# PDM_v1.net
KiCad netlist of a schematic drawn in EAGLE
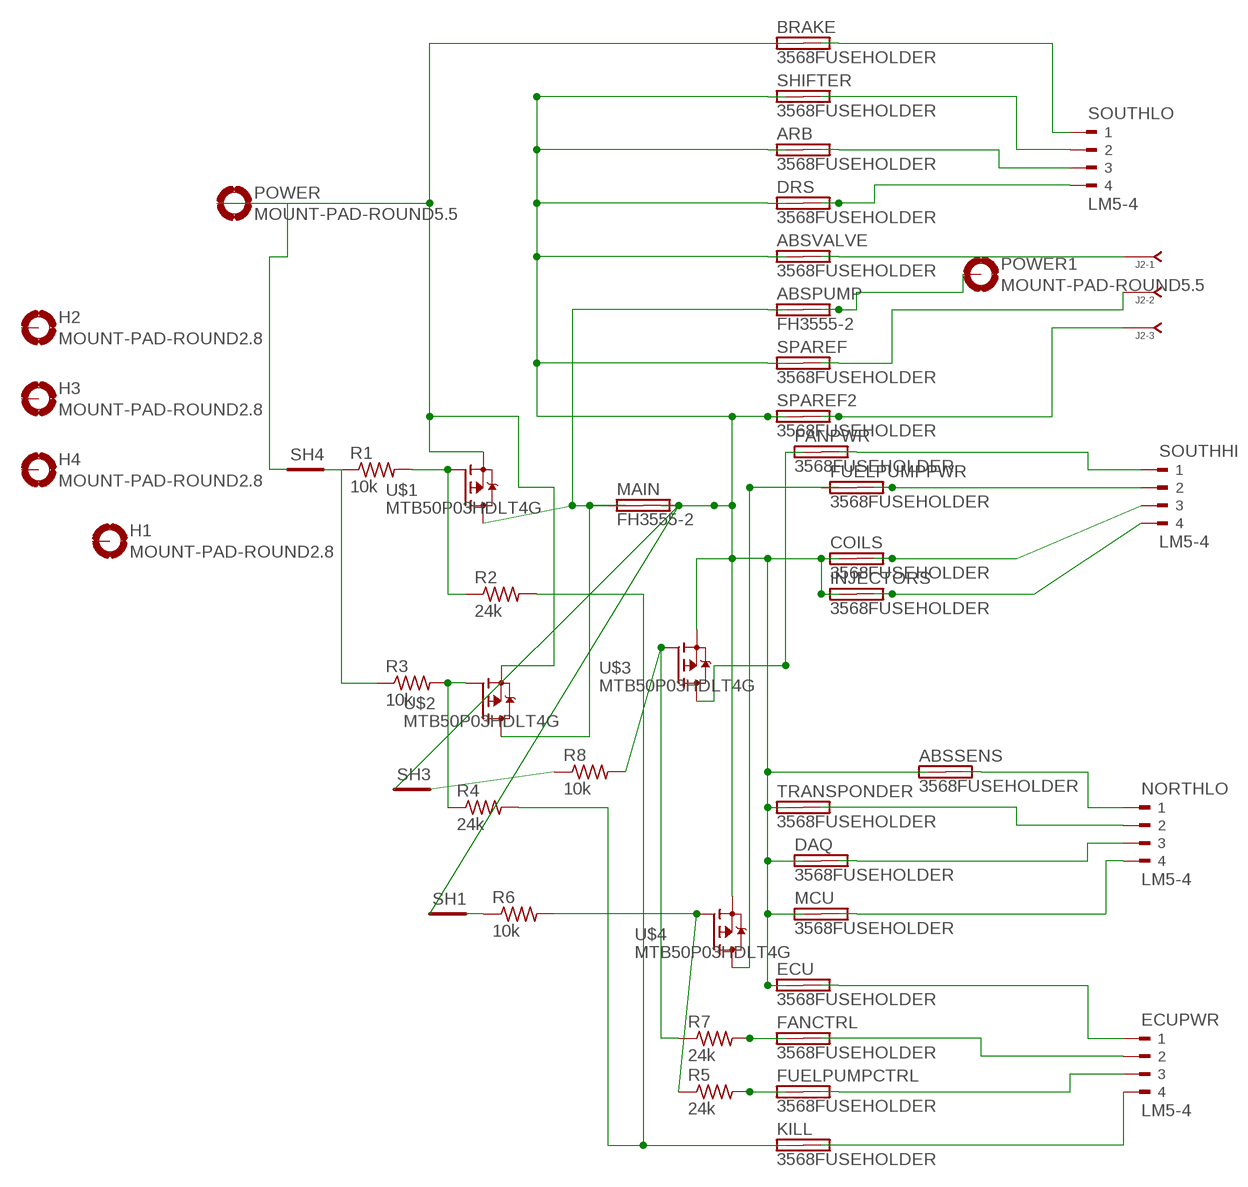
[diagram p0: schematic, sheet 1]

(export (version "E")
  (design (tool "Eeschema 10.0.6"))
  (components
    (comp (ref "ABSPUMP")
      (value "FH3555-2")
      (footprint "eagle-import:3555-2")
      (libsource (lib "eagle-import") (part "FH3555-2"))
    )
    (comp (ref "ABSSENS")
      (value "3568FUSEHOLDER")
      (footprint "eagle-import:3568")
      (libsource (lib "eagle-import") (part "3568FUSEHOLDER"))
    )
    (comp (ref "ABSVALVE")
      (value "3568FUSEHOLDER")
      (footprint "eagle-import:3568")
      (libsource (lib "eagle-import") (part "3568FUSEHOLDER"))
    )
    (comp (ref "ARB")
      (value "3568FUSEHOLDER")
      (footprint "eagle-import:3568")
      (libsource (lib "eagle-import") (part "3568FUSEHOLDER"))
    )
    (comp (ref "BRAKE")
      (value "3568FUSEHOLDER")
      (footprint "eagle-import:3568")
      (libsource (lib "eagle-import") (part "3568FUSEHOLDER"))
    )
    (comp (ref "COILS")
      (value "3568FUSEHOLDER")
      (footprint "eagle-import:3568")
      (libsource (lib "eagle-import") (part "3568FUSEHOLDER"))
    )
    (comp (ref "DAQ")
      (value "3568FUSEHOLDER")
      (footprint "eagle-import:3568")
      (libsource (lib "eagle-import") (part "3568FUSEHOLDER"))
    )
    (comp (ref "DRS")
      (value "3568FUSEHOLDER")
      (footprint "eagle-import:3568")
      (libsource (lib "eagle-import") (part "3568FUSEHOLDER"))
    )
    (comp (ref "ECU")
      (value "3568FUSEHOLDER")
      (footprint "eagle-import:3568")
      (libsource (lib "eagle-import") (part "3568FUSEHOLDER"))
    )
    (comp (ref "ECUPWR")
      (value "LM5-4")
      (footprint "eagle-import:281-1423")
      (libsource (lib "eagle-import") (part "LM5-4"))
    )
    (comp (ref "FANCTRL")
      (value "3568FUSEHOLDER")
      (footprint "eagle-import:3568")
      (libsource (lib "eagle-import") (part "3568FUSEHOLDER"))
    )
    (comp (ref "FANPWR")
      (value "3568FUSEHOLDER")
      (footprint "eagle-import:3568")
      (libsource (lib "eagle-import") (part "3568FUSEHOLDER"))
    )
    (comp (ref "FUELPUMPCTRL")
      (value "3568FUSEHOLDER")
      (footprint "eagle-import:3568")
      (libsource (lib "eagle-import") (part "3568FUSEHOLDER"))
    )
    (comp (ref "FUELPUMPPWR")
      (value "3568FUSEHOLDER")
      (footprint "eagle-import:3568")
      (libsource (lib "eagle-import") (part "3568FUSEHOLDER"))
    )
    (comp (ref "H1")
      (value "MOUNT-PAD-ROUND2.8")
      (footprint "eagle-import:2,8-PAD")
      (libsource (lib "eagle-import") (part "MOUNT-PAD-ROUND2.8"))
    )
    (comp (ref "H2")
      (value "MOUNT-PAD-ROUND2.8")
      (footprint "eagle-import:2,8-PAD")
      (libsource (lib "eagle-import") (part "MOUNT-PAD-ROUND2.8"))
    )
    (comp (ref "H3")
      (value "MOUNT-PAD-ROUND2.8")
      (footprint "eagle-import:2,8-PAD")
      (libsource (lib "eagle-import") (part "MOUNT-PAD-ROUND2.8"))
    )
    (comp (ref "H4")
      (value "MOUNT-PAD-ROUND2.8")
      (footprint "eagle-import:2,8-PAD")
      (libsource (lib "eagle-import") (part "MOUNT-PAD-ROUND2.8"))
    )
    (comp (ref "INJECTORS")
      (value "3568FUSEHOLDER")
      (footprint "eagle-import:3568")
      (libsource (lib "eagle-import") (part "3568FUSEHOLDER"))
    )
    (comp (ref "J2")
      (value "J-04-")
      (footprint "eagle-import:535512-04")
      (libsource (lib "eagle-import") (part "J-04-"))
    )
    (comp (ref "KILL")
      (value "3568FUSEHOLDER")
      (footprint "eagle-import:3568")
      (libsource (lib "eagle-import") (part "3568FUSEHOLDER"))
    )
    (comp (ref "MAIN")
      (value "FH3555-2")
      (footprint "eagle-import:3555-2")
      (libsource (lib "eagle-import") (part "FH3555-2"))
    )
    (comp (ref "MCU")
      (value "3568FUSEHOLDER")
      (footprint "eagle-import:3568")
      (libsource (lib "eagle-import") (part "3568FUSEHOLDER"))
    )
    (comp (ref "NORTHLO")
      (value "LM5-4")
      (footprint "eagle-import:281-1423")
      (libsource (lib "eagle-import") (part "LM5-4"))
    )
    (comp (ref "POWER")
      (value "MOUNT-PAD-ROUND5.5")
      (footprint "eagle-import:5,5-PAD")
      (libsource (lib "eagle-import") (part "MOUNT-PAD-ROUND5.5"))
    )
    (comp (ref "POWER1")
      (value "MOUNT-PAD-ROUND5.5")
      (footprint "eagle-import:5,5-PAD")
      (libsource (lib "eagle-import") (part "MOUNT-PAD-ROUND5.5"))
    )
    (comp (ref "R1")
      (value "10k")
      (footprint "eagle-import:M0805")
      (libsource (lib "eagle-import") (part "R-US_M0805"))
    )
    (comp (ref "R2")
      (value "24k")
      (footprint "eagle-import:M0805")
      (libsource (lib "eagle-import") (part "R-US_M0805"))
    )
    (comp (ref "R3")
      (value "10k")
      (footprint "eagle-import:M0805")
      (libsource (lib "eagle-import") (part "R-US_M0805"))
    )
    (comp (ref "R4")
      (value "24k")
      (footprint "eagle-import:M0805")
      (libsource (lib "eagle-import") (part "R-US_M0805"))
    )
    (comp (ref "R5")
      (value "24k")
      (footprint "eagle-import:M0805")
      (libsource (lib "eagle-import") (part "R-US_M0805"))
    )
    (comp (ref "R6")
      (value "10k")
      (footprint "eagle-import:M0805")
      (libsource (lib "eagle-import") (part "R-US_M0805"))
    )
    (comp (ref "R7")
      (value "24k")
      (footprint "eagle-import:M0805")
      (libsource (lib "eagle-import") (part "R-US_M0805"))
    )
    (comp (ref "R8")
      (value "10k")
      (footprint "eagle-import:M0805")
      (libsource (lib "eagle-import") (part "R-US_M0805"))
    )
    (comp (ref "SH1")
      (value "SHORTA5")
      (footprint "eagle-import:SHORT_ALL-50")
      (libsource (lib "eagle-import") (part "SHORTA5"))
    )
    (comp (ref "SH3")
      (value "SHORTA5")
      (footprint "eagle-import:SHORT_ALL-50")
      (libsource (lib "eagle-import") (part "SHORTA5"))
    )
    (comp (ref "SH4")
      (value "SHORTA5")
      (footprint "eagle-import:SHORT_ALL-50")
      (libsource (lib "eagle-import") (part "SHORTA5"))
    )
    (comp (ref "SHIFTER")
      (value "3568FUSEHOLDER")
      (footprint "eagle-import:3568")
      (libsource (lib "eagle-import") (part "3568FUSEHOLDER"))
    )
    (comp (ref "SOUTHHI")
      (value "LM5-4")
      (footprint "eagle-import:281-1423")
      (libsource (lib "eagle-import") (part "LM5-4"))
    )
    (comp (ref "SOUTHLO")
      (value "LM5-4")
      (footprint "eagle-import:281-1423")
      (libsource (lib "eagle-import") (part "LM5-4"))
    )
    (comp (ref "SPAREF")
      (value "3568FUSEHOLDER")
      (footprint "eagle-import:3568")
      (libsource (lib "eagle-import") (part "3568FUSEHOLDER"))
    )
    (comp (ref "SPAREF2")
      (value "3568FUSEHOLDER")
      (footprint "eagle-import:3568")
      (libsource (lib "eagle-import") (part "3568FUSEHOLDER"))
    )
    (comp (ref "TRANSPONDER")
      (value "3568FUSEHOLDER")
      (footprint "eagle-import:3568")
      (libsource (lib "eagle-import") (part "3568FUSEHOLDER"))
    )
    (comp (ref "U$1")
      (value "MTB50P03HDLT4G")
      (footprint "eagle-import:TO263")
      (libsource (lib "eagle-import") (part "MTB50P03HDLT4G"))
    )
    (comp (ref "U$2")
      (value "MTB50P03HDLT4G")
      (footprint "eagle-import:TO263")
      (libsource (lib "eagle-import") (part "MTB50P03HDLT4G"))
    )
    (comp (ref "U$3")
      (value "MTB50P03HDLT4G")
      (footprint "eagle-import:TO263")
      (libsource (lib "eagle-import") (part "MTB50P03HDLT4G"))
    )
    (comp (ref "U$4")
      (value "MTB50P03HDLT4G")
      (footprint "eagle-import:TO263")
      (libsource (lib "eagle-import") (part "MTB50P03HDLT4G"))
    )
  )
  (nets
    (net (code "1") (name "Net-(ABSPUMP-1A)") (class "Default")
      (node (ref "ABSPUMP") (pin "L1") (pinfunction "1A_L1") (pintype "passive"))
      (node (ref "ABSPUMP") (pin "L2") (pinfunction "1B_L2") (pintype "passive"))
      (node (ref "MAIN") (pin "L1") (pinfunction "1A_L1") (pintype "passive"))
      (node (ref "MAIN") (pin "L2") (pinfunction "1B_L2") (pintype "passive"))
      (node (ref "U$1") (pin "3") (pinfunction "D_3") (pintype "passive"))
      (node (ref "U$2") (pin "3") (pinfunction "D_3") (pintype "passive"))
    )
    (net (code "2") (name "Net-(ABSPUMP-2A)") (class "Default")
      (node (ref "ABSPUMP") (pin "R1") (pinfunction "2A_R1") (pintype "passive"))
      (node (ref "ABSPUMP") (pin "R2") (pinfunction "2B_R2") (pintype "passive"))
      (node (ref "POWER1") (pin "B5,5") (pinfunction "MOUNT_B5,5") (pintype "passive"))
    )
    (net (code "3") (name "Net-(ABSSENS-1A)") (class "Default")
      (node (ref "ABSSENS") (pin "L1") (pinfunction "1A_L1") (pintype "passive"))
      (node (ref "ABSSENS") (pin "L2") (pinfunction "1B_L2") (pintype "passive"))
      (node (ref "ABSVALVE") (pin "L1") (pinfunction "1A_L1") (pintype "passive"))
      (node (ref "ABSVALVE") (pin "L2") (pinfunction "1B_L2") (pintype "passive"))
      (node (ref "ARB") (pin "L1") (pinfunction "1A_L1") (pintype "passive"))
      (node (ref "ARB") (pin "L2") (pinfunction "1B_L2") (pintype "passive"))
      (node (ref "COILS") (pin "L1") (pinfunction "1A_L1") (pintype "passive"))
      (node (ref "COILS") (pin "L2") (pinfunction "1B_L2") (pintype "passive"))
      (node (ref "DAQ") (pin "L1") (pinfunction "1A_L1") (pintype "passive"))
      (node (ref "DAQ") (pin "L2") (pinfunction "1B_L2") (pintype "passive"))
      (node (ref "DRS") (pin "L1") (pinfunction "1A_L1") (pintype "passive"))
      (node (ref "DRS") (pin "L2") (pinfunction "1B_L2") (pintype "passive"))
      (node (ref "ECU") (pin "L1") (pinfunction "1A_L1") (pintype "passive"))
      (node (ref "ECU") (pin "L2") (pinfunction "1B_L2") (pintype "passive"))
      (node (ref "INJECTORS") (pin "L1") (pinfunction "1A_L1") (pintype "passive"))
      (node (ref "INJECTORS") (pin "L2") (pinfunction "1B_L2") (pintype "passive"))
      (node (ref "MAIN") (pin "R1") (pinfunction "2A_R1") (pintype "passive"))
      (node (ref "MAIN") (pin "R2") (pinfunction "2B_R2") (pintype "passive"))
      (node (ref "MCU") (pin "L1") (pinfunction "1A_L1") (pintype "passive"))
      (node (ref "MCU") (pin "L2") (pinfunction "1B_L2") (pintype "passive"))
      (node (ref "SH1") (pin "1") (pinfunction "P$1_1") (pintype "bidirectional"))
      (node (ref "SH3") (pin "1") (pinfunction "P$1_1") (pintype "bidirectional"))
      (node (ref "SHIFTER") (pin "L1") (pinfunction "1A_L1") (pintype "passive"))
      (node (ref "SHIFTER") (pin "L2") (pinfunction "1B_L2") (pintype "passive"))
      (node (ref "SPAREF") (pin "L1") (pinfunction "1A_L1") (pintype "passive"))
      (node (ref "SPAREF") (pin "L2") (pinfunction "1B_L2") (pintype "passive"))
      (node (ref "SPAREF2") (pin "L1") (pinfunction "1A_L1") (pintype "passive"))
      (node (ref "SPAREF2") (pin "L2") (pinfunction "1B_L2") (pintype "passive"))
      (node (ref "TRANSPONDER") (pin "L1") (pinfunction "1A_L1") (pintype "passive"))
      (node (ref "TRANSPONDER") (pin "L2") (pinfunction "1B_L2") (pintype "passive"))
      (node (ref "U$3") (pin "2") (pinfunction "S_2") (pintype "passive"))
      (node (ref "U$4") (pin "2") (pinfunction "S_2") (pintype "passive"))
    )
    (net (code "4") (name "Net-(ABSSENS-2A)") (class "Default")
      (node (ref "ABSSENS") (pin "R1") (pinfunction "2A_R1") (pintype "passive"))
      (node (ref "ABSSENS") (pin "R2") (pinfunction "2B_R2") (pintype "passive"))
      (node (ref "NORTHLO") (pin "P$1") (pinfunction "1_P$1") (pintype "passive"))
    )
    (net (code "5") (name "Net-(ABSVALVE-2A)") (class "Default")
      (node (ref "ABSVALVE") (pin "R1") (pinfunction "2A_R1") (pintype "passive"))
      (node (ref "ABSVALVE") (pin "R2") (pinfunction "2B_R2") (pintype "passive"))
      (node (ref "J2") (pin "LEFT") (pinfunction "J_LEFT") (pintype "passive"))
    )
    (net (code "6") (name "Net-(ARB-2A)") (class "Default")
      (node (ref "ARB") (pin "R1") (pinfunction "2A_R1") (pintype "passive"))
      (node (ref "ARB") (pin "R2") (pinfunction "2B_R2") (pintype "passive"))
      (node (ref "SOUTHLO") (pin "P$3") (pinfunction "3_P$3") (pintype "passive"))
    )
    (net (code "7") (name "Net-(BRAKE-1A)") (class "Default")
      (node (ref "BRAKE") (pin "L1") (pinfunction "1A_L1") (pintype "passive"))
      (node (ref "BRAKE") (pin "L2") (pinfunction "1B_L2") (pintype "passive"))
      (node (ref "POWER") (pin "B5,5") (pinfunction "MOUNT_B5,5") (pintype "passive"))
      (node (ref "SH4") (pin "1") (pinfunction "P$1_1") (pintype "bidirectional"))
      (node (ref "U$1") (pin "2") (pinfunction "S_2") (pintype "passive"))
      (node (ref "U$2") (pin "2") (pinfunction "S_2") (pintype "passive"))
    )
    (net (code "8") (name "Net-(BRAKE-2A)") (class "Default")
      (node (ref "BRAKE") (pin "R1") (pinfunction "2A_R1") (pintype "passive"))
      (node (ref "BRAKE") (pin "R2") (pinfunction "2B_R2") (pintype "passive"))
      (node (ref "SOUTHLO") (pin "P$1") (pinfunction "1_P$1") (pintype "passive"))
    )
    (net (code "9") (name "Net-(COILS-2A)") (class "Default")
      (node (ref "COILS") (pin "R1") (pinfunction "2A_R1") (pintype "passive"))
      (node (ref "COILS") (pin "R2") (pinfunction "2B_R2") (pintype "passive"))
      (node (ref "SOUTHHI") (pin "P$3") (pinfunction "3_P$3") (pintype "passive"))
    )
    (net (code "10") (name "Net-(DAQ-2A)") (class "Default")
      (node (ref "DAQ") (pin "R1") (pinfunction "2A_R1") (pintype "passive"))
      (node (ref "DAQ") (pin "R2") (pinfunction "2B_R2") (pintype "passive"))
      (node (ref "NORTHLO") (pin "P$3") (pinfunction "3_P$3") (pintype "passive"))
    )
    (net (code "11") (name "Net-(DRS-2A)") (class "Default")
      (node (ref "DRS") (pin "R1") (pinfunction "2A_R1") (pintype "passive"))
      (node (ref "DRS") (pin "R2") (pinfunction "2B_R2") (pintype "passive"))
      (node (ref "SOUTHLO") (pin "P$4") (pinfunction "4_P$4") (pintype "passive"))
    )
    (net (code "12") (name "Net-(ECU-2A)") (class "Default")
      (node (ref "ECU") (pin "R1") (pinfunction "2A_R1") (pintype "passive"))
      (node (ref "ECU") (pin "R2") (pinfunction "2B_R2") (pintype "passive"))
      (node (ref "ECUPWR") (pin "P$1") (pinfunction "1_P$1") (pintype "passive"))
    )
    (net (code "13") (name "Net-(ECUPWR-2)") (class "Default")
      (node (ref "ECUPWR") (pin "P$2") (pinfunction "2_P$2") (pintype "passive"))
      (node (ref "FANCTRL") (pin "R1") (pinfunction "2A_R1") (pintype "passive"))
      (node (ref "FANCTRL") (pin "R2") (pinfunction "2B_R2") (pintype "passive"))
    )
    (net (code "14") (name "Net-(ECUPWR-3)") (class "Default")
      (node (ref "ECUPWR") (pin "P$3") (pinfunction "3_P$3") (pintype "passive"))
      (node (ref "FUELPUMPCTRL") (pin "R1") (pinfunction "2A_R1") (pintype "passive"))
      (node (ref "FUELPUMPCTRL") (pin "R2") (pinfunction "2B_R2") (pintype "passive"))
    )
    (net (code "15") (name "Net-(ECUPWR-4)") (class "Default")
      (node (ref "ECUPWR") (pin "P$4") (pinfunction "4_P$4") (pintype "passive"))
      (node (ref "KILL") (pin "R1") (pinfunction "2A_R1") (pintype "passive"))
      (node (ref "KILL") (pin "R2") (pinfunction "2B_R2") (pintype "passive"))
    )
    (net (code "16") (name "Net-(FANCTRL-1A)") (class "Default")
      (node (ref "FANCTRL") (pin "L1") (pinfunction "1A_L1") (pintype "passive"))
      (node (ref "FANCTRL") (pin "L2") (pinfunction "1B_L2") (pintype "passive"))
      (node (ref "R7") (pin "2") (pinfunction "2_2") (pintype "passive"))
    )
    (net (code "17") (name "Net-(FANPWR-1A)") (class "Default")
      (node (ref "FANPWR") (pin "L1") (pinfunction "1A_L1") (pintype "passive"))
      (node (ref "FANPWR") (pin "L2") (pinfunction "1B_L2") (pintype "passive"))
      (node (ref "U$3") (pin "3") (pinfunction "D_3") (pintype "passive"))
    )
    (net (code "18") (name "Net-(FANPWR-2A)") (class "Default")
      (node (ref "FANPWR") (pin "R1") (pinfunction "2A_R1") (pintype "passive"))
      (node (ref "FANPWR") (pin "R2") (pinfunction "2B_R2") (pintype "passive"))
      (node (ref "SOUTHHI") (pin "P$1") (pinfunction "1_P$1") (pintype "passive"))
    )
    (net (code "19") (name "Net-(FUELPUMPCTRL-1A)") (class "Default")
      (node (ref "FUELPUMPCTRL") (pin "L1") (pinfunction "1A_L1") (pintype "passive"))
      (node (ref "FUELPUMPCTRL") (pin "L2") (pinfunction "1B_L2") (pintype "passive"))
      (node (ref "R5") (pin "2") (pinfunction "2_2") (pintype "passive"))
    )
    (net (code "20") (name "Net-(FUELPUMPPWR-1A)") (class "Default")
      (node (ref "FUELPUMPPWR") (pin "L1") (pinfunction "1A_L1") (pintype "passive"))
      (node (ref "FUELPUMPPWR") (pin "L2") (pinfunction "1B_L2") (pintype "passive"))
      (node (ref "U$4") (pin "3") (pinfunction "D_3") (pintype "passive"))
    )
    (net (code "21") (name "Net-(FUELPUMPPWR-2A)") (class "Default")
      (node (ref "FUELPUMPPWR") (pin "R1") (pinfunction "2A_R1") (pintype "passive"))
      (node (ref "FUELPUMPPWR") (pin "R2") (pinfunction "2B_R2") (pintype "passive"))
      (node (ref "SOUTHHI") (pin "P$2") (pinfunction "2_P$2") (pintype "passive"))
    )
    (net (code "22") (name "Net-(INJECTORS-2A)") (class "Default")
      (node (ref "INJECTORS") (pin "R1") (pinfunction "2A_R1") (pintype "passive"))
      (node (ref "INJECTORS") (pin "R2") (pinfunction "2B_R2") (pintype "passive"))
      (node (ref "SOUTHHI") (pin "P$4") (pinfunction "4_P$4") (pintype "passive"))
    )
    (net (code "23") (name "Net-(J2B-J)") (class "Default")
      (node (ref "J2") (pin "MIDDLE") (pinfunction "J_MIDDLE") (pintype "passive"))
      (node (ref "SPAREF") (pin "R1") (pinfunction "2A_R1") (pintype "passive"))
      (node (ref "SPAREF") (pin "R2") (pinfunction "2B_R2") (pintype "passive"))
    )
    (net (code "24") (name "Net-(J2C-J)") (class "Default")
      (node (ref "J2") (pin "RIGHT") (pinfunction "J_RIGHT") (pintype "passive"))
      (node (ref "SPAREF2") (pin "R1") (pinfunction "2A_R1") (pintype "passive"))
      (node (ref "SPAREF2") (pin "R2") (pinfunction "2B_R2") (pintype "passive"))
    )
    (net (code "25") (name "Net-(KILL-1A)") (class "Default")
      (node (ref "KILL") (pin "L1") (pinfunction "1A_L1") (pintype "passive"))
      (node (ref "KILL") (pin "L2") (pinfunction "1B_L2") (pintype "passive"))
      (node (ref "R2") (pin "2") (pinfunction "2_2") (pintype "passive"))
      (node (ref "R4") (pin "2") (pinfunction "2_2") (pintype "passive"))
    )
    (net (code "26") (name "Net-(MCU-2A)") (class "Default")
      (node (ref "MCU") (pin "R1") (pinfunction "2A_R1") (pintype "passive"))
      (node (ref "MCU") (pin "R2") (pinfunction "2B_R2") (pintype "passive"))
      (node (ref "NORTHLO") (pin "P$4") (pinfunction "4_P$4") (pintype "passive"))
    )
    (net (code "27") (name "Net-(NORTHLO-2)") (class "Default")
      (node (ref "NORTHLO") (pin "P$2") (pinfunction "2_P$2") (pintype "passive"))
      (node (ref "TRANSPONDER") (pin "R1") (pinfunction "2A_R1") (pintype "passive"))
      (node (ref "TRANSPONDER") (pin "R2") (pinfunction "2B_R2") (pintype "passive"))
    )
    (net (code "28") (name "Net-(SH1-P$2)") (class "Default")
      (node (ref "R6") (pin "1") (pinfunction "1_1") (pintype "passive"))
      (node (ref "SH1") (pin "2") (pinfunction "P$2_2") (pintype "bidirectional"))
    )
    (net (code "29") (name "Net-(SH3-P$2)") (class "Default")
      (node (ref "R8") (pin "1") (pinfunction "1_1") (pintype "passive"))
      (node (ref "SH3") (pin "2") (pinfunction "P$2_2") (pintype "bidirectional"))
    )
    (net (code "30") (name "Net-(SH4-P$2)") (class "Default")
      (node (ref "R1") (pin "1") (pinfunction "1_1") (pintype "passive"))
      (node (ref "R3") (pin "1") (pinfunction "1_1") (pintype "passive"))
      (node (ref "SH4") (pin "2") (pinfunction "P$2_2") (pintype "bidirectional"))
    )
    (net (code "31") (name "Net-(SHIFTER-2A)") (class "Default")
      (node (ref "SHIFTER") (pin "R1") (pinfunction "2A_R1") (pintype "passive"))
      (node (ref "SHIFTER") (pin "R2") (pinfunction "2B_R2") (pintype "passive"))
      (node (ref "SOUTHLO") (pin "P$2") (pinfunction "2_P$2") (pintype "passive"))
    )
    (net (code "32") (name "Net-(U$1-G)") (class "Default")
      (node (ref "R1") (pin "2") (pinfunction "2_2") (pintype "passive"))
      (node (ref "R2") (pin "1") (pinfunction "1_1") (pintype "passive"))
      (node (ref "U$1") (pin "1") (pinfunction "G_1") (pintype "passive"))
    )
    (net (code "33") (name "Net-(U$2-G)") (class "Default")
      (node (ref "R3") (pin "2") (pinfunction "2_2") (pintype "passive"))
      (node (ref "R4") (pin "1") (pinfunction "1_1") (pintype "passive"))
      (node (ref "U$2") (pin "1") (pinfunction "G_1") (pintype "passive"))
    )
    (net (code "34") (name "Net-(U$3-G)") (class "Default")
      (node (ref "R7") (pin "1") (pinfunction "1_1") (pintype "passive"))
      (node (ref "R8") (pin "2") (pinfunction "2_2") (pintype "passive"))
      (node (ref "U$3") (pin "1") (pinfunction "G_1") (pintype "passive"))
    )
    (net (code "35") (name "Net-(U$4-G)") (class "Default")
      (node (ref "R5") (pin "1") (pinfunction "1_1") (pintype "passive"))
      (node (ref "R6") (pin "2") (pinfunction "2_2") (pintype "passive"))
      (node (ref "U$4") (pin "1") (pinfunction "G_1") (pintype "passive"))
    )
    (net (code "36") (name "unconnected-(H1-MOUNT-PadB2,8)") (class "Default")
      (node (ref "H1") (pin "B2,8") (pinfunction "MOUNT_B2,8") (pintype "passive"))
    )
    (net (code "37") (name "unconnected-(H2-MOUNT-PadB2,8)") (class "Default")
      (node (ref "H2") (pin "B2,8") (pinfunction "MOUNT_B2,8") (pintype "passive"))
    )
    (net (code "38") (name "unconnected-(H3-MOUNT-PadB2,8)") (class "Default")
      (node (ref "H3") (pin "B2,8") (pinfunction "MOUNT_B2,8") (pintype "passive"))
    )
    (net (code "39") (name "unconnected-(H4-MOUNT-PadB2,8)") (class "Default")
      (node (ref "H4") (pin "B2,8") (pinfunction "MOUNT_B2,8") (pintype "passive"))
    )
  )
)
